# Driver1.net
KiCad netlist of a schematic drawn in Altium Designer
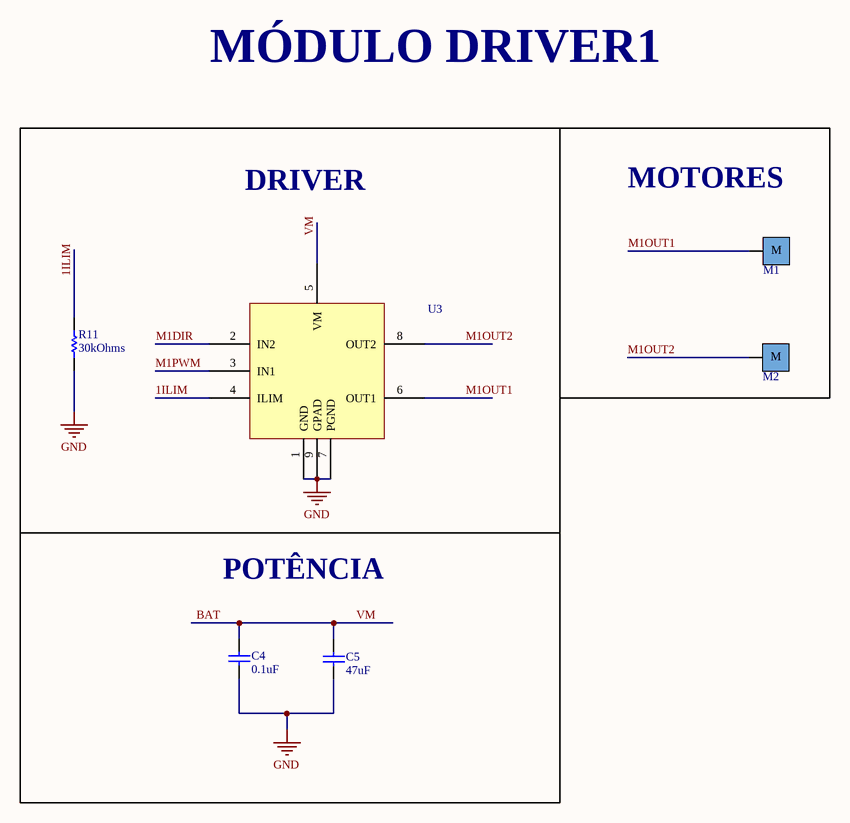
[diagram p0: Driver1.SchDoc]

(export (version "E")
  (design (tool "Eeschema 10.0.6"))
  (components
    (comp (ref "C4")
      (value "0.1uF")
      (footprint "C0805")
      (description "CAP CER 100nF 25V X7R 0805")
      (fields
        (field (name "MANUFACTURER") "Kemet")
        (field (name "PART NUMBER") "C0805C104M3RACTU")
        (field (name "LIBRARY CONTROL - PERSON THAT CHECKED FOOTPRINT") "Cage")
        (field (name "LIBRARY CONTROL - PERSON THAT CHECKED SCHEMATIC") "Cage")
        (field (name "LIBRARY CONTROL - PERSON THAT DID THE LAST UPDATE FOOTPRINT") "Cage")
        (field (name "LIBRARY CONTROL - PERSON THAT DID THE LAST UPDATE SCHEMATIC") "Cage")
      )
      (libsource (lib "Uai!Tecas") (part "C0805C104M3RACTU"))
    )
    (comp (ref "C5")
      (value "47uF")
      (footprint "C1210")
      (description "CAP CER 47uF 16V X6S 1210")
      (fields
        (field (name "MANUFACTURER") "Murata")
        (field (name "PART NUMBER") "GRM32EC81C476KE15K")
        (field (name "LIBRARY CONTROL - PERSON THAT CHECKED FOOTPRINT") "Cage")
        (field (name "LIBRARY CONTROL - PERSON THAT CHECKED SCHEMATIC") "Cage")
        (field (name "LIBRARY CONTROL - PERSON THAT DID THE LAST UPDATE FOOTPRINT") "Prisma")
        (field (name "LIBRARY CONTROL - PERSON THAT DID THE LAST UPDATE SCHEMATIC") "Prisma")
      )
      (libsource (lib "Capacitor") (part "GRM32EC81C476KE15K"))
    )
    (comp (ref "M1")
      (value "Motor Pad")
      (footprint "PAD_MOTOR_MINI")
      (description "MOTOR PAD MINI SUMÔ")
      (libsource (lib "Uai!Tecas") (part "Motor Pad Mini Sumô"))
    )
    (comp (ref "M2")
      (value "Motor Pad")
      (footprint "PAD_MOTOR_MINI")
      (description "MOTOR PAD MINI SUMÔ")
      (libsource (lib "Uai!Tecas") (part "Motor Pad Mini Sumô"))
    )
    (comp (ref "R11")
      (value "30kOhms")
      (footprint "RESC1608X55N")
      (description "RES SMD 30 kOHMS 1% 1/10W 0603")
      (fields
        (field (name "MANUFACTURER") "YAGEO")
        (field (name "PART NUMBER") "RC0603FR-0730KL")
        (field (name "LIBRARY CONTROL - PERSON THAT CHECKED FOOTPRINT") "Guilherme")
        (field (name "LIBRARY CONTROL - PERSON THAT CHECKED SCHEMATIC") "Guilherme")
        (field (name "LIBRARY CONTROL - PERSON THAT DID THE LAST UPDATE FOOTPRINT") "Guilherme")
        (field (name "LIBRARY CONTROL - PERSON THAT DID THE LAST UPDATE SCHEMATIC") "Guilherme")
      )
      (libsource (lib "Uai!Tecas") (part "RC0603FR-0730KL"))
    )
    (comp (ref "U3")
      (value "DRV8871DDA")
      (footprint "SO-PowerPad-8(8_pins)")
      (description "IC MTR DRV (6.5V ~ 45V) (3.5 A) SO-PowerPad-8")
      (fields
        (field (name "MANUFACTURER") "Texas Instruments")
        (field (name "LIBRARY CONTROL - PERSON THAT CHECKED SCHEMATIC") "Stéfany (Ster)")
        (field (name "LIBRARY CONTROL - PERSON THAT CHECKED FOOTPRINT") "Stéfany (Ster)")
        (field (name "LIBRARY CONTROL - PERSON THAT DID THE LAST UPDATE SCHEMATIC") "Stéfany (Ster)")
        (field (name "LIBRARY CONTROL - PERSON THAT DID THE LAST UPDATE FOOTPRINT") "Maria Laura")
      )
      (libsource (lib "Uai!Tecas") (part "DRV8871DDA"))
    )
  )
  (nets
    (net (code "1") (name "/1ILIM") (class "Default")
      (node (ref "R11") (pin "1") (pinfunction "1_1") (pintype "passive"))
      (node (ref "U3") (pin "4") (pinfunction "ILIM_4") (pintype "passive"))
    )
    (net (code "2") (name "/BAT") (class "Default")
      (node (ref "C4") (pin "2") (pinfunction "2_2") (pintype "passive"))
      (node (ref "C5") (pin "2") (pinfunction "2_2") (pintype "passive"))
      (node (ref "U3") (pin "5") (pinfunction "VM_5") (pintype "passive"))
    )
    (net (code "3") (name "/M1DIR") (class "Default")
      (node (ref "U3") (pin "2") (pinfunction "IN2_2") (pintype "passive"))
    )
    (net (code "4") (name "/M1OUT1") (class "Default")
      (node (ref "M1") (pin "M") (pinfunction "M_M") (pintype "passive"))
      (node (ref "U3") (pin "6") (pinfunction "OUT1_6") (pintype "passive"))
    )
    (net (code "5") (name "/M1OUT2") (class "Default")
      (node (ref "M2") (pin "M") (pinfunction "M_M") (pintype "passive"))
      (node (ref "U3") (pin "8") (pinfunction "OUT2_8") (pintype "passive"))
    )
    (net (code "6") (name "/M1PWM") (class "Default")
      (node (ref "U3") (pin "3") (pinfunction "IN1_3") (pintype "passive"))
    )
    (net (code "7") (name "GND") (class "Default")
      (node (ref "C4") (pin "1") (pinfunction "1_1") (pintype "passive"))
      (node (ref "C5") (pin "1") (pinfunction "1_1") (pintype "passive"))
      (node (ref "R11") (pin "2") (pinfunction "2_2") (pintype "passive"))
      (node (ref "U3") (pin "1") (pinfunction "GND_1") (pintype "passive"))
      (node (ref "U3") (pin "7") (pinfunction "PGND_7") (pintype "passive"))
      (node (ref "U3") (pin "9") (pinfunction "GPAD_9") (pintype "passive"))
    )
  )
)
